# rotary_table_v2.net
KiCad netlist of a schematic drawn in Altium Designer
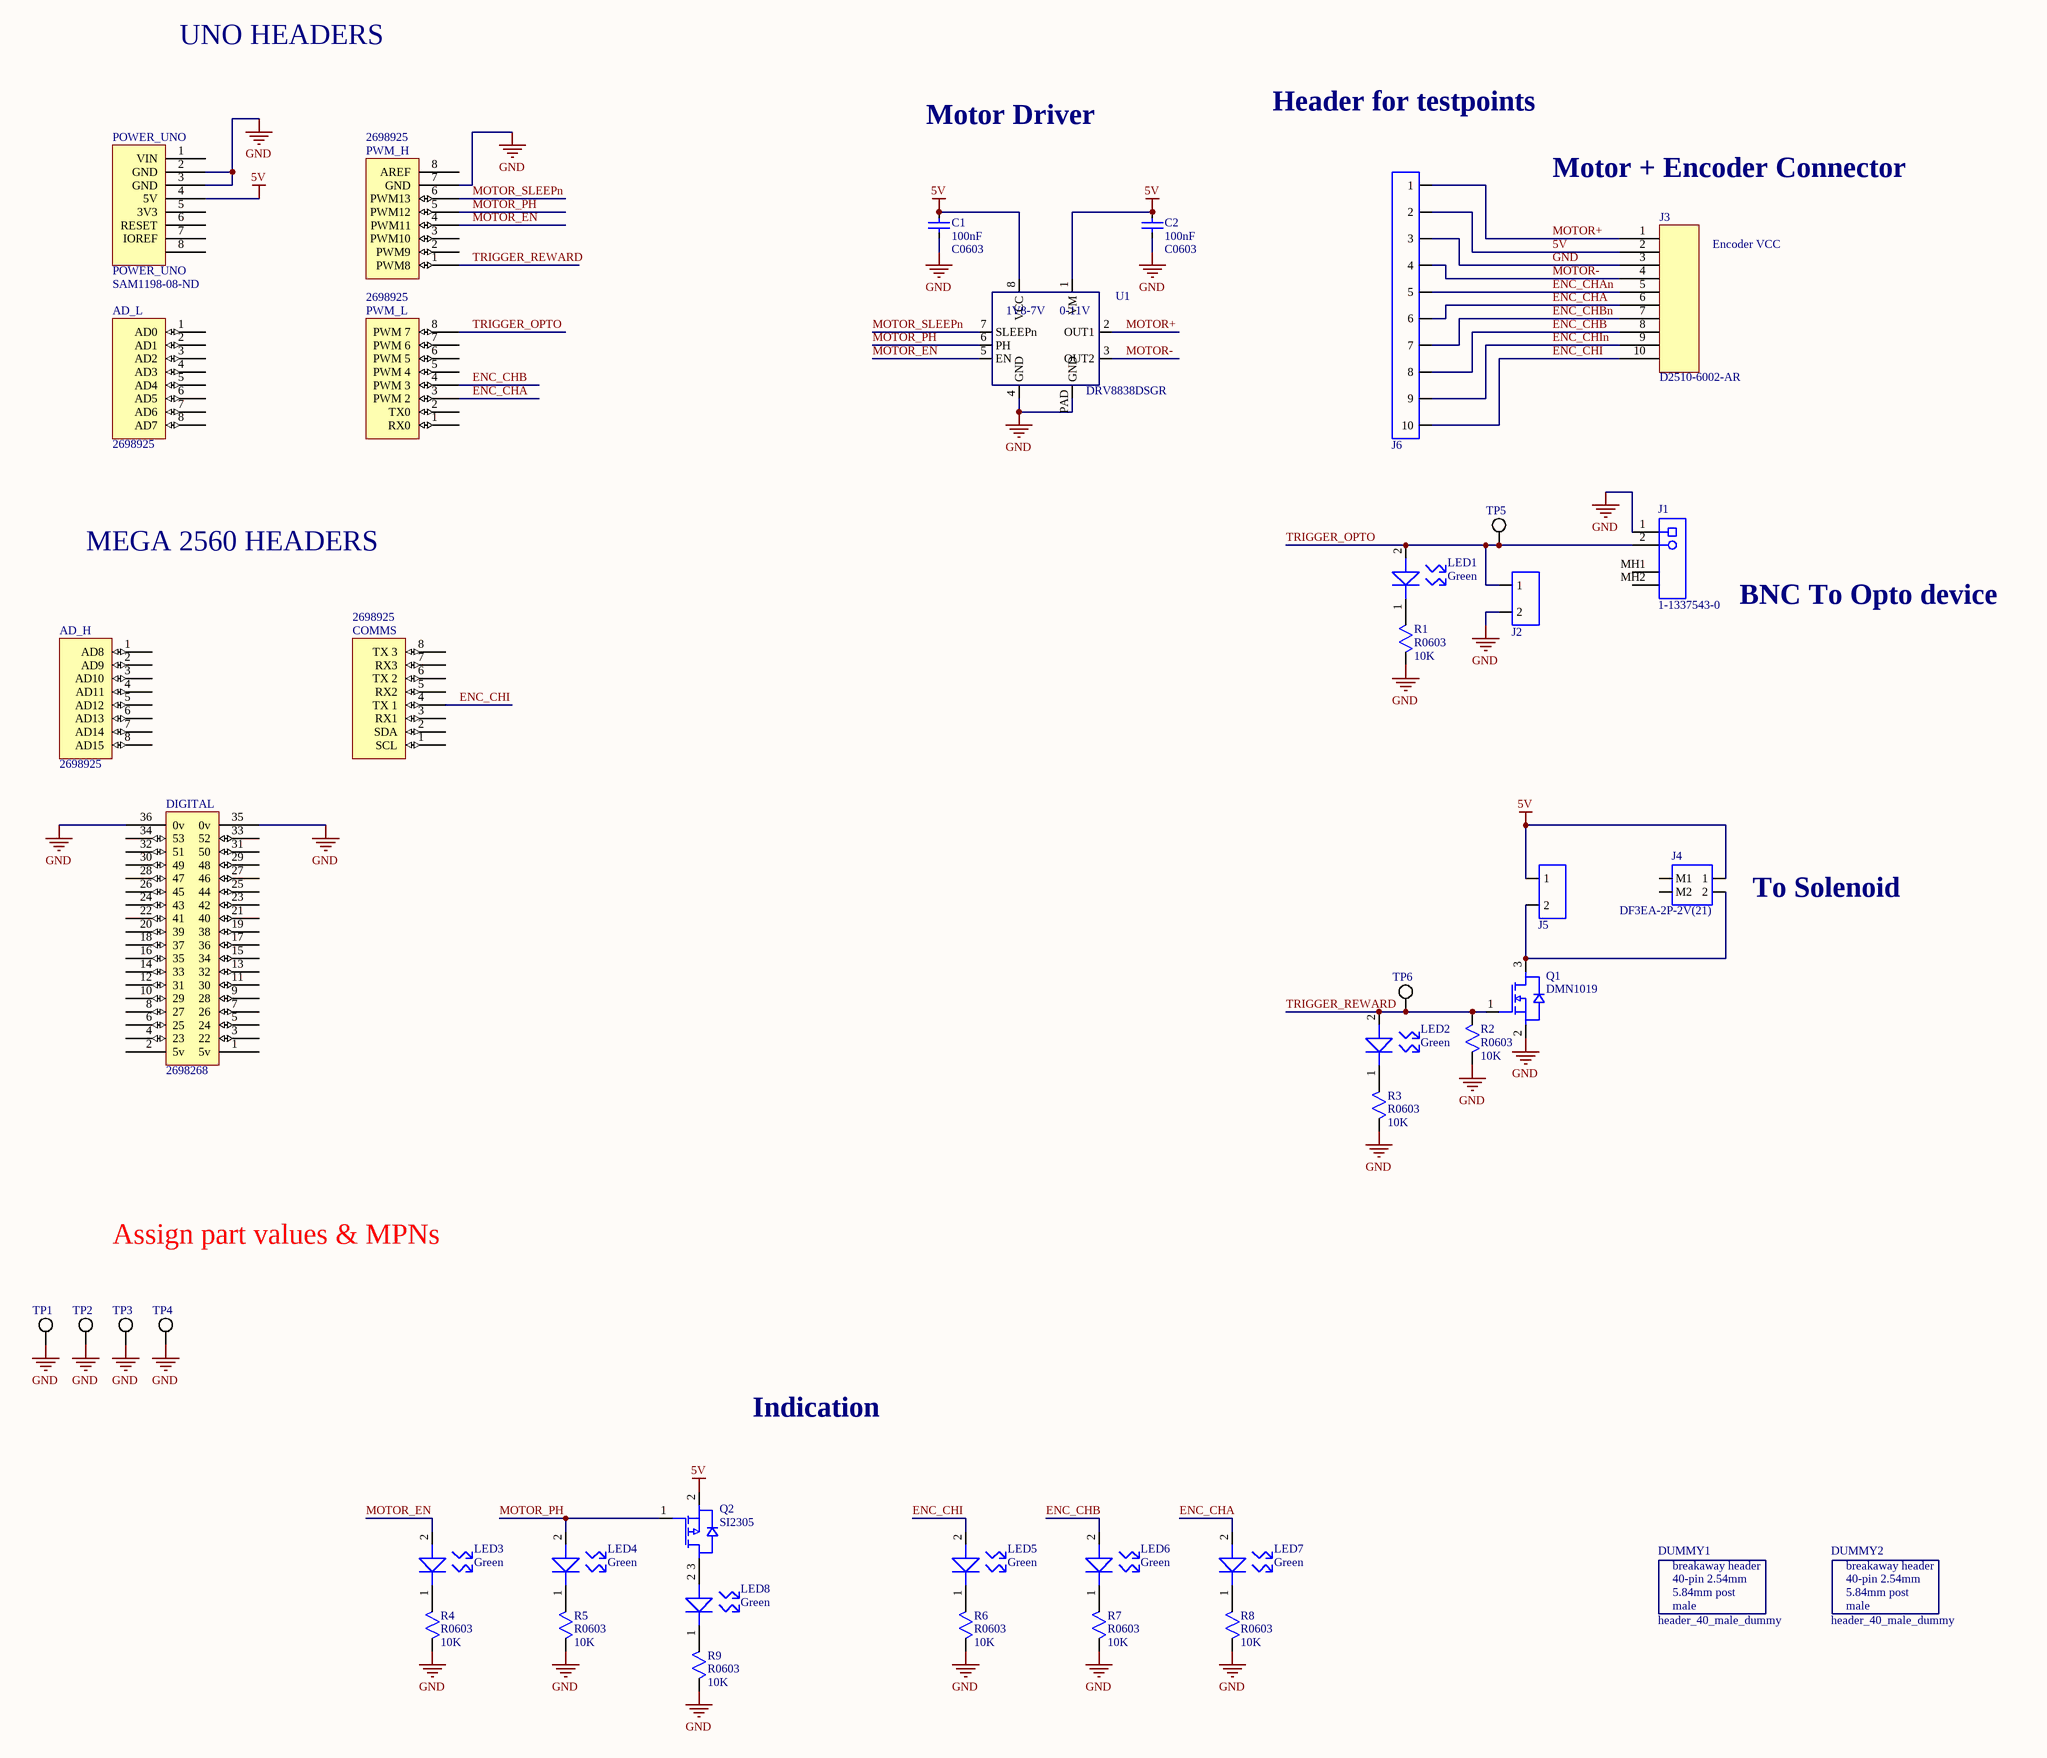
[diagram p0: rotary_table_v2.SchDoc]

(export (version "E")
  (design (tool "Eeschema 10.0.6"))
  (components
    (comp (ref "AD_H")
      (value "AD_H")
      (footprint "Header 8x1 8.5mm")
      (fields (field (name "SUPPLIER PART NUMBER 4") "2698925"))
      (libsource (lib "Header") (part "AD_H"))
    )
    (comp (ref "AD_L")
      (value "AD_L")
      (footprint "Header 8x1 8.5mm")
      (fields (field (name "SUPPLIER PART NUMBER 5") "2698925"))
      (libsource (lib "Header") (part "AD_L"))
    )
    (comp (ref "C1")
      (value "100nF")
      (footprint "C0603")
      (description "Nonpolarized capacitor")
      (fields
        (field (name "DIGIKEYPARTNUMBER") "1276-CL10B104KC8VPNCCT-ND")
        (field (name "MANUFACTURER") "Samsung")
      )
      (libsource (lib "Mark_Library") (part "CAP"))
    )
    (comp (ref "C2")
      (value "100nF")
      (footprint "C0603")
      (description "Nonpolarized capacitor")
      (fields
        (field (name "DIGIKEYPARTNUMBER") "1276-CL10B104KC8VPNCCT-ND")
        (field (name "MANUFACTURER") "Samsung")
      )
      (libsource (lib "Mark_Library") (part "CAP"))
    )
    (comp (ref "COMMS")
      (value "Communication")
      (footprint "Header 8x1 8.5mm")
      (fields (field (name "SUPPLIER PART NUMBER 4") "2698925"))
      (libsource (lib "Header") (part "Communication"))
    )
    (comp (ref "DIGITAL")
      (value "IO_36")
      (footprint "HEADER 36X 8MM")
      (fields (field (name "SUPPLIER PART NUMBER 5") "2698268"))
      (libsource (lib "Header") (part "IO_36"))
    )
    (comp (ref "DUMMY1")
      (value "header_40_male_dummy")
      (description "row of 40 pins breakaway male 2.54mm")
      (fields (field (name "MANUFACTURER") "Sullins") (field (name "MFGPARTNUMBER") "PRPC040SAAN-RC"))
      (libsource (lib "Mark_Library") (part "header_40_male_dummy"))
    )
    (comp (ref "DUMMY2")
      (value "header_40_male_dummy")
      (description "row of 40 pins breakaway male 2.54mm")
      (fields (field (name "MANUFACTURER") "Sullins") (field (name "MFGPARTNUMBER") "PRPC040SAAN-RC"))
      (libsource (lib "Mark_Library") (part "header_40_male_dummy"))
    )
    (comp (ref "J1")
      (value "1-1337543-0")
      (footprint "TECO-1-1337543-0_V")
      (fields (field (name "MANUFACTURER") "TE Connectivity") (field (name "DIGIKEYPARTNUMBER") "A97553-ND"))
      (libsource (lib "Altium Content Vault") (part "CN-1P-F-R2_A"))
    )
    (comp (ref "J2")
      (value "0.1in 2x1")
      (footprint "HEADER_2x1")
      (description "0.1in header 2x1")
      (libsource (lib "Mark_Library") (part "HEADER_2x1"))
    )
    (comp (ref "J3")
      (value "D2510-6002-AR")
      (footprint "D2510-6002")
      (description "CONN HEADER 10POS VERT 10GOLD")
      (fields
        (field (name "MANUFACTURER") "3M")
        (field (name "MANUFACTURER PART NUMBER") "D2510-6002-AR")
        (field (name "DIGIKEYPARTNUMBER") "MHC10E-ND")
      )
      (libsource (lib "UCSD Protolab") (part "D2510-6002-AR"))
    )
    (comp (ref "J4")
      (value "DF3EA-2P-2V(21)")
      (footprint "DF3EA-2P-2V(21)")
      (description "CONN HEADER SMD 2POS 2MM")
      (fields
        (field (name "MANUFACTURER") "Hirose")
        (field (name "DIGIKEYPARTNUMBER") "H125461CT-ND")
        (field (name "MFGPARTNUMBER") "DF3EA-2P-2V(21)")
      )
      (libsource (lib "Mark_Library") (part "DF3EA-2P-2V(21)"))
    )
    (comp (ref "J5")
      (value "0.1in 2x1")
      (footprint "HEADER_2x1")
      (description "0.1in header 2x1")
      (libsource (lib "Mark_Library") (part "HEADER_2x1"))
    )
    (comp (ref "J6")
      (value "0.1in 10x1")
      (footprint "HEADER_10x1")
      (description "0.1in header 10x1")
      (libsource (lib "Mark_Library") (part "HEADER_10x1"))
    )
    (comp (ref "LED1")
      (value "Green")
      (footprint "LED0603")
      (description "LED")
      (fields
        (field (name "MANUFACTURER") "Wurth Elektronik")
        (field (name "MFGPARTNUMBER") "150060VS75000")
        (field (name "COLOR") "Green")
      )
      (libsource (lib "Mark_Library") (part "LED"))
    )
    (comp (ref "LED2")
      (value "Green")
      (footprint "LED0603")
      (description "LED")
      (fields
        (field (name "MANUFACTURER") "Wurth Elektronik")
        (field (name "MFGPARTNUMBER") "150060VS75000")
        (field (name "COLOR") "Green")
      )
      (libsource (lib "Mark_Library") (part "LED"))
    )
    (comp (ref "LED3")
      (value "Green")
      (footprint "LED0603")
      (description "LED")
      (fields
        (field (name "MANUFACTURER") "Wurth Elektronik")
        (field (name "MFGPARTNUMBER") "150060VS75000")
        (field (name "COLOR") "Green")
      )
      (libsource (lib "Mark_Library") (part "LED"))
    )
    (comp (ref "LED4")
      (value "Green")
      (footprint "LED0603")
      (description "LED")
      (fields
        (field (name "MANUFACTURER") "Wurth Elektronik")
        (field (name "MFGPARTNUMBER") "150060VS75000")
        (field (name "COLOR") "Green")
      )
      (libsource (lib "Mark_Library") (part "LED"))
    )
    (comp (ref "LED5")
      (value "Green")
      (footprint "LED0603")
      (description "LED")
      (fields
        (field (name "MANUFACTURER") "Wurth Elektronik")
        (field (name "MFGPARTNUMBER") "150060VS75000")
        (field (name "COLOR") "Green")
      )
      (libsource (lib "Mark_Library") (part "LED"))
    )
    (comp (ref "LED6")
      (value "Green")
      (footprint "LED0603")
      (description "LED")
      (fields
        (field (name "MANUFACTURER") "Wurth Elektronik")
        (field (name "MFGPARTNUMBER") "150060VS75000")
        (field (name "COLOR") "Green")
      )
      (libsource (lib "Mark_Library") (part "LED"))
    )
    (comp (ref "LED7")
      (value "Green")
      (footprint "LED0603")
      (description "LED")
      (fields
        (field (name "MANUFACTURER") "Wurth Elektronik")
        (field (name "MFGPARTNUMBER") "150060VS75000")
        (field (name "COLOR") "Green")
      )
      (libsource (lib "Mark_Library") (part "LED"))
    )
    (comp (ref "LED8")
      (value "Green")
      (footprint "LED0603")
      (description "LED")
      (fields
        (field (name "MANUFACTURER") "Wurth Elektronik")
        (field (name "MFGPARTNUMBER") "150060VS75000")
        (field (name "COLOR") "Green")
      )
      (libsource (lib "Mark_Library") (part "LED"))
    )
    (comp (ref "POWER_UNO")
      (value "POWER_UNO")
      (footprint "Header 8x1 8.5mm")
      (fields (field (name "SUPPLIER PART NUMBER 2") "SAM1198-08-ND"))
      (libsource (lib "Header") (part "POWER_UNO"))
    )
    (comp (ref "PWM_H")
      (value "PWM_H")
      (footprint "Header 8x1 8.5mm")
      (fields (field (name "SUPPLIER PART NUMBER 4") "2698925"))
      (libsource (lib "Header") (part "PWM_H"))
    )
    (comp (ref "PWM_L")
      (value "PWM_L")
      (footprint "Header 8x1 8.5mm")
      (fields (field (name "SUPPLIER PART NUMBER 4") "2698925"))
      (libsource (lib "Header") (part "PWM_L"))
    )
    (comp (ref "Q1")
      (value "DMN1019")
      (footprint "SC59-3")
      (description "MOSFET N-CH 12V 9.3A SC59")
      (fields
        (field (name "MANUFACTURER") "Diodes Incorporated")
        (field (name "MFGPARTNUMBER") "DMN1019USN-7")
      )
      (libsource (lib "Mark_Library") (part "DMN1019UVT"))
    )
    (comp (ref "Q2")
      (value "SI2305")
      (footprint "SOT23-3")
      (description "P-CHANNEL MOSFET, SOT-23 PACKAGE")
      (fields (field (name "MANUFACTURER") "Micro Commercial Co") (field (name "MFGPARTNUMBER") "SI2305-TP"))
      (libsource (lib "Mark_Library") (part "SI2305"))
    )
    (comp (ref "R1")
      (value "10K")
      (footprint "R0603")
      (description "Resistor")
      (fields (field (name "MANUFACTURER") "Stackpole") (field (name "MFGPARTNUMBER") "RMCF0603FT10K0"))
      (libsource (lib "Mark_Library") (part "RES"))
    )
    (comp (ref "R2")
      (value "10K")
      (footprint "R0603")
      (description "Resistor")
      (fields (field (name "MANUFACTURER") "Stackpole") (field (name "MFGPARTNUMBER") "RMCF0603FT10K0"))
      (libsource (lib "Mark_Library") (part "RES"))
    )
    (comp (ref "R3")
      (value "10K")
      (footprint "R0603")
      (description "Resistor")
      (fields (field (name "MANUFACTURER") "Stackpole") (field (name "MFGPARTNUMBER") "RMCF0603FT10K0"))
      (libsource (lib "Mark_Library") (part "RES"))
    )
    (comp (ref "R4")
      (value "10K")
      (footprint "R0603")
      (description "Resistor")
      (fields (field (name "MANUFACTURER") "Stackpole") (field (name "MFGPARTNUMBER") "RMCF0603FT10K0"))
      (libsource (lib "Mark_Library") (part "RES"))
    )
    (comp (ref "R5")
      (value "10K")
      (footprint "R0603")
      (description "Resistor")
      (fields (field (name "MANUFACTURER") "Stackpole") (field (name "MFGPARTNUMBER") "RMCF0603FT10K0"))
      (libsource (lib "Mark_Library") (part "RES"))
    )
    (comp (ref "R6")
      (value "10K")
      (footprint "R0603")
      (description "Resistor")
      (fields (field (name "MANUFACTURER") "Stackpole") (field (name "MFGPARTNUMBER") "RMCF0603FT10K0"))
      (libsource (lib "Mark_Library") (part "RES"))
    )
    (comp (ref "R7")
      (value "10K")
      (footprint "R0603")
      (description "Resistor")
      (fields (field (name "MANUFACTURER") "Stackpole") (field (name "MFGPARTNUMBER") "RMCF0603FT10K0"))
      (libsource (lib "Mark_Library") (part "RES"))
    )
    (comp (ref "R8")
      (value "10K")
      (footprint "R0603")
      (description "Resistor")
      (fields (field (name "MANUFACTURER") "Stackpole") (field (name "MFGPARTNUMBER") "RMCF0603FT10K0"))
      (libsource (lib "Mark_Library") (part "RES"))
    )
    (comp (ref "R9")
      (value "10K")
      (footprint "R0603")
      (description "Resistor")
      (fields (field (name "MANUFACTURER") "Stackpole") (field (name "MFGPARTNUMBER") "RMCF0603FT10K0"))
      (libsource (lib "Mark_Library") (part "RES"))
    )
    (comp (ref "TP1")
      (value "GND")
      (footprint "TP_0IN1")
      (description "hole for 0.1in header. No BOM item.")
      (libsource (lib "Mark_Library") (part "TP_0IN1"))
    )
    (comp (ref "TP2")
      (value "GND")
      (footprint "TP_0IN1")
      (description "hole for 0.1in header. No BOM item.")
      (libsource (lib "Mark_Library") (part "TP_0IN1"))
    )
    (comp (ref "TP3")
      (value "GND")
      (footprint "TP_0IN1")
      (description "hole for 0.1in header. No BOM item.")
      (libsource (lib "Mark_Library") (part "TP_0IN1"))
    )
    (comp (ref "TP4")
      (value "GND")
      (footprint "TP_0IN1")
      (description "hole for 0.1in header. No BOM item.")
      (libsource (lib "Mark_Library") (part "TP_0IN1"))
    )
    (comp (ref "TP5")
      (value "OPTO")
      (footprint "TP_0IN1")
      (description "hole for 0.1in header. No BOM item.")
      (libsource (lib "Mark_Library") (part "TP_0IN1"))
    )
    (comp (ref "TP6")
      (value "REWARD")
      (footprint "TP_0IN1")
      (description "hole for 0.1in header. No BOM item.")
      (libsource (lib "Mark_Library") (part "TP_0IN1"))
    )
    (comp (ref "U1")
      (value "DRV8838DSGR")
      (footprint "WSON-8_PAD")
      (description "IC BRIDGE DRIVER PAR 8WSON")
      (fields
        (field (name "MANUFACTURER") "Texas Instruments")
        (field (name "MFGPARTNUMBER") "DRV8838DSGR")
        (field (name "DIGIKEYPARTNUMBER") "296-40081-1-ND")
      )
      (libsource (lib "Mark_Library") (part "DRV8838DSGR"))
    )
  )
  (nets
    (net (code "1") (name "/ENC_CHA") (class "Default")
      (node (ref "J3") (pin "6") (pintype "passive"))
      (node (ref "J6") (pin "6") (pinfunction "6_6") (pintype "passive"))
      (node (ref "LED7") (pin "2") (pinfunction "2_2") (pintype "passive"))
      (node (ref "PWM_L") (pin "3") (pinfunction "PWM_2_3") (pintype "bidirectional"))
    )
    (net (code "2") (name "/ENC_CHAn") (class "Default")
      (node (ref "J3") (pin "5") (pintype "passive"))
      (node (ref "J6") (pin "5") (pinfunction "5_5") (pintype "passive"))
    )
    (net (code "3") (name "/ENC_CHB") (class "Default")
      (node (ref "J3") (pin "8") (pintype "passive"))
      (node (ref "J6") (pin "8") (pinfunction "8_8") (pintype "passive"))
      (node (ref "LED6") (pin "2") (pinfunction "2_2") (pintype "passive"))
      (node (ref "PWM_L") (pin "4") (pinfunction "PWM_3_4") (pintype "bidirectional"))
    )
    (net (code "4") (name "/ENC_CHBn") (class "Default")
      (node (ref "J3") (pin "7") (pintype "passive"))
      (node (ref "J6") (pin "7") (pinfunction "7_7") (pintype "passive"))
    )
    (net (code "5") (name "/ENC_CHI") (class "Default")
      (node (ref "COMMS") (pin "4") (pinfunction "TX_1_4") (pintype "bidirectional"))
      (node (ref "J3") (pin "10") (pintype "passive"))
      (node (ref "J6") (pin "10") (pinfunction "10_10") (pintype "passive"))
      (node (ref "LED5") (pin "2") (pinfunction "2_2") (pintype "passive"))
    )
    (net (code "6") (name "/ENC_CHIn") (class "Default")
      (node (ref "J3") (pin "9") (pintype "passive"))
      (node (ref "J6") (pin "9") (pinfunction "9_9") (pintype "passive"))
    )
    (net (code "7") (name "/MOTOR+") (class "Default")
      (node (ref "J3") (pin "1") (pintype "passive"))
      (node (ref "J6") (pin "1") (pinfunction "1_1") (pintype "passive"))
      (node (ref "U1") (pin "2") (pinfunction "OUT1_2") (pintype "passive"))
    )
    (net (code "8") (name "/MOTOR-") (class "Default")
      (node (ref "J3") (pin "4") (pintype "passive"))
      (node (ref "J6") (pin "4") (pinfunction "4_4") (pintype "passive"))
      (node (ref "U1") (pin "3") (pinfunction "OUT2_3") (pintype "passive"))
    )
    (net (code "9") (name "/MOTOR_EN") (class "Default")
      (node (ref "LED3") (pin "2") (pinfunction "2_2") (pintype "passive"))
      (node (ref "PWM_H") (pin "4") (pinfunction "PWM11_4") (pintype "bidirectional"))
      (node (ref "U1") (pin "5") (pinfunction "EN_5") (pintype "passive"))
    )
    (net (code "10") (name "/MOTOR_PH") (class "Default")
      (node (ref "LED4") (pin "2") (pinfunction "2_2") (pintype "passive"))
      (node (ref "PWM_H") (pin "5") (pinfunction "PWM12_5") (pintype "bidirectional"))
      (node (ref "Q2") (pin "1") (pinfunction "1_1") (pintype "passive"))
      (node (ref "U1") (pin "6") (pinfunction "PH_6") (pintype "passive"))
    )
    (net (code "11") (name "/MOTOR_SLEEPn") (class "Default")
      (node (ref "PWM_H") (pin "6") (pinfunction "PWM13_6") (pintype "bidirectional"))
      (node (ref "U1") (pin "7") (pinfunction "SLEEPn_7") (pintype "passive"))
    )
    (net (code "12") (name "/TRIGGER_OPTO") (class "Default")
      (node (ref "J1") (pin "2") (pinfunction "2_2") (pintype "passive"))
      (node (ref "J2") (pin "1") (pinfunction "1_1") (pintype "passive"))
      (node (ref "LED1") (pin "2") (pinfunction "2_2") (pintype "passive"))
      (node (ref "PWM_L") (pin "8") (pinfunction "PWM_7_8") (pintype "bidirectional"))
      (node (ref "TP5") (pin "1") (pinfunction "MTG_1") (pintype "passive"))
    )
    (net (code "13") (name "/TRIGGER_REWARD") (class "Default")
      (node (ref "LED2") (pin "2") (pinfunction "2_2") (pintype "passive"))
      (node (ref "PWM_H") (pin "1") (pinfunction "PWM8_1") (pintype "bidirectional"))
      (node (ref "Q1") (pin "1") (pinfunction "1_1") (pintype "passive"))
      (node (ref "R2") (pin "1") (pinfunction "1_1") (pintype "passive"))
      (node (ref "TP6") (pin "1") (pinfunction "MTG_1") (pintype "passive"))
    )
    (net (code "14") (name "5V") (class "Default")
      (node (ref "C1") (pin "2") (pinfunction "2_2") (pintype "passive"))
      (node (ref "C2") (pin "2") (pinfunction "2_2") (pintype "passive"))
      (node (ref "J3") (pin "2") (pintype "passive"))
      (node (ref "J4") (pin "1") (pinfunction "1_1") (pintype "passive"))
      (node (ref "J5") (pin "1") (pinfunction "1_1") (pintype "passive"))
      (node (ref "J6") (pin "2") (pinfunction "2_2") (pintype "passive"))
      (node (ref "POWER_UNO") (pin "4") (pinfunction "5V_4") (pintype "power_in"))
      (node (ref "Q2") (pin "2") (pinfunction "2_2") (pintype "passive"))
      (node (ref "U1") (pin "1") (pinfunction "VM_1") (pintype "passive"))
      (node (ref "U1") (pin "8") (pinfunction "VCC_8") (pintype "passive"))
    )
    (net (code "15") (name "GND") (class "Default")
      (node (ref "C1") (pin "1") (pinfunction "1_1") (pintype "passive"))
      (node (ref "C2") (pin "1") (pinfunction "1_1") (pintype "passive"))
      (node (ref "DIGITAL") (pin "35") (pinfunction "0v_35") (pintype "power_in"))
      (node (ref "DIGITAL") (pin "36") (pinfunction "0v_36") (pintype "power_in"))
      (node (ref "J1") (pin "1") (pinfunction "1_1") (pintype "passive"))
      (node (ref "J2") (pin "2") (pinfunction "2_2") (pintype "passive"))
      (node (ref "J3") (pin "3") (pintype "passive"))
      (node (ref "J6") (pin "3") (pinfunction "3_3") (pintype "passive"))
      (node (ref "POWER_UNO") (pin "2") (pinfunction "GND_2") (pintype "power_in"))
      (node (ref "POWER_UNO") (pin "3") (pinfunction "GND_3") (pintype "power_in"))
      (node (ref "PWM_H") (pin "7") (pinfunction "GND_7") (pintype "power_in"))
      (node (ref "Q1") (pin "2") (pinfunction "2_2") (pintype "passive"))
      (node (ref "R1") (pin "2") (pinfunction "2_2") (pintype "passive"))
      (node (ref "R2") (pin "2") (pinfunction "2_2") (pintype "passive"))
      (node (ref "R3") (pin "2") (pinfunction "2_2") (pintype "passive"))
      (node (ref "R4") (pin "2") (pinfunction "2_2") (pintype "passive"))
      (node (ref "R5") (pin "2") (pinfunction "2_2") (pintype "passive"))
      (node (ref "R6") (pin "2") (pinfunction "2_2") (pintype "passive"))
      (node (ref "R7") (pin "2") (pinfunction "2_2") (pintype "passive"))
      (node (ref "R8") (pin "2") (pinfunction "2_2") (pintype "passive"))
      (node (ref "R9") (pin "2") (pinfunction "2_2") (pintype "passive"))
      (node (ref "TP1") (pin "1") (pinfunction "MTG_1") (pintype "passive"))
      (node (ref "TP2") (pin "1") (pinfunction "MTG_1") (pintype "passive"))
      (node (ref "TP3") (pin "1") (pinfunction "MTG_1") (pintype "passive"))
      (node (ref "TP4") (pin "1") (pinfunction "MTG_1") (pintype "passive"))
      (node (ref "U1") (pin "4") (pinfunction "GND_4") (pintype "passive"))
      (node (ref "U1") (pin "PAD") (pinfunction "GND_PAD") (pintype "passive"))
    )
    (net (code "16") (name "Net-(J4-Pad2)") (class "Default")
      (node (ref "J4") (pin "2") (pinfunction "2_2") (pintype "passive"))
      (node (ref "J5") (pin "2") (pinfunction "2_2") (pintype "passive"))
      (node (ref "Q1") (pin "3") (pinfunction "3_3") (pintype "passive"))
    )
    (net (code "17") (name "Net-(LED1-Pad1)") (class "Default")
      (node (ref "LED1") (pin "1") (pinfunction "1_1") (pintype "passive"))
      (node (ref "R1") (pin "1") (pinfunction "1_1") (pintype "passive"))
    )
    (net (code "18") (name "Net-(LED2-Pad1)") (class "Default")
      (node (ref "LED2") (pin "1") (pinfunction "1_1") (pintype "passive"))
      (node (ref "R3") (pin "1") (pinfunction "1_1") (pintype "passive"))
    )
    (net (code "19") (name "Net-(LED3-Pad1)") (class "Default")
      (node (ref "LED3") (pin "1") (pinfunction "1_1") (pintype "passive"))
      (node (ref "R4") (pin "1") (pinfunction "1_1") (pintype "passive"))
    )
    (net (code "20") (name "Net-(LED4-Pad1)") (class "Default")
      (node (ref "LED4") (pin "1") (pinfunction "1_1") (pintype "passive"))
      (node (ref "R5") (pin "1") (pinfunction "1_1") (pintype "passive"))
    )
    (net (code "21") (name "Net-(LED5-Pad1)") (class "Default")
      (node (ref "LED5") (pin "1") (pinfunction "1_1") (pintype "passive"))
      (node (ref "R6") (pin "1") (pinfunction "1_1") (pintype "passive"))
    )
    (net (code "22") (name "Net-(LED6-Pad1)") (class "Default")
      (node (ref "LED6") (pin "1") (pinfunction "1_1") (pintype "passive"))
      (node (ref "R7") (pin "1") (pinfunction "1_1") (pintype "passive"))
    )
    (net (code "23") (name "Net-(LED7-Pad1)") (class "Default")
      (node (ref "LED7") (pin "1") (pinfunction "1_1") (pintype "passive"))
      (node (ref "R8") (pin "1") (pinfunction "1_1") (pintype "passive"))
    )
    (net (code "24") (name "Net-(LED8-Pad1)") (class "Default")
      (node (ref "LED8") (pin "1") (pinfunction "1_1") (pintype "passive"))
      (node (ref "R9") (pin "1") (pinfunction "1_1") (pintype "passive"))
    )
    (net (code "25") (name "Net-(LED8-Pad2)") (class "Default")
      (node (ref "LED8") (pin "2") (pinfunction "2_2") (pintype "passive"))
      (node (ref "Q2") (pin "3") (pinfunction "3_3") (pintype "passive"))
    )
    (net (code "26") (name "unconnected-(AD_H-AD8-Pad1)") (class "Default")
      (node (ref "AD_H") (pin "1") (pinfunction "AD8_1") (pintype "bidirectional"))
    )
    (net (code "27") (name "unconnected-(AD_H-AD9-Pad2)") (class "Default")
      (node (ref "AD_H") (pin "2") (pinfunction "AD9_2") (pintype "bidirectional"))
    )
    (net (code "28") (name "unconnected-(AD_H-AD10-Pad3)") (class "Default")
      (node (ref "AD_H") (pin "3") (pinfunction "AD10_3") (pintype "bidirectional"))
    )
    (net (code "29") (name "unconnected-(AD_H-AD11-Pad4)") (class "Default")
      (node (ref "AD_H") (pin "4") (pinfunction "AD11_4") (pintype "bidirectional"))
    )
    (net (code "30") (name "unconnected-(AD_H-AD12-Pad5)") (class "Default")
      (node (ref "AD_H") (pin "5") (pinfunction "AD12_5") (pintype "bidirectional"))
    )
    (net (code "31") (name "unconnected-(AD_H-AD13-Pad6)") (class "Default")
      (node (ref "AD_H") (pin "6") (pinfunction "AD13_6") (pintype "bidirectional"))
    )
    (net (code "32") (name "unconnected-(AD_H-AD14-Pad7)") (class "Default")
      (node (ref "AD_H") (pin "7") (pinfunction "AD14_7") (pintype "bidirectional"))
    )
    (net (code "33") (name "unconnected-(AD_H-AD15-Pad8)") (class "Default")
      (node (ref "AD_H") (pin "8") (pinfunction "AD15_8") (pintype "bidirectional"))
    )
    (net (code "34") (name "unconnected-(AD_L-AD0-Pad1)") (class "Default")
      (node (ref "AD_L") (pin "1") (pinfunction "AD0_1") (pintype "bidirectional"))
    )
    (net (code "35") (name "unconnected-(AD_L-AD1-Pad2)") (class "Default")
      (node (ref "AD_L") (pin "2") (pinfunction "AD1_2") (pintype "bidirectional"))
    )
    (net (code "36") (name "unconnected-(AD_L-AD2-Pad3)") (class "Default")
      (node (ref "AD_L") (pin "3") (pinfunction "AD2_3") (pintype "bidirectional"))
    )
    (net (code "37") (name "unconnected-(AD_L-AD3-Pad4)") (class "Default")
      (node (ref "AD_L") (pin "4") (pinfunction "AD3_4") (pintype "bidirectional"))
    )
    (net (code "38") (name "unconnected-(AD_L-AD4-Pad5)") (class "Default")
      (node (ref "AD_L") (pin "5") (pinfunction "AD4_5") (pintype "bidirectional"))
    )
    (net (code "39") (name "unconnected-(AD_L-AD5-Pad6)") (class "Default")
      (node (ref "AD_L") (pin "6") (pinfunction "AD5_6") (pintype "bidirectional"))
    )
    (net (code "40") (name "unconnected-(AD_L-AD6-Pad7)") (class "Default")
      (node (ref "AD_L") (pin "7") (pinfunction "AD6_7") (pintype "bidirectional"))
    )
    (net (code "41") (name "unconnected-(AD_L-AD7-Pad8)") (class "Default")
      (node (ref "AD_L") (pin "8") (pinfunction "AD7_8") (pintype "bidirectional"))
    )
    (net (code "42") (name "unconnected-(COMMS-RX1-Pad3)") (class "Default")
      (node (ref "COMMS") (pin "3") (pinfunction "RX1_3") (pintype "bidirectional"))
    )
    (net (code "43") (name "unconnected-(COMMS-RX2-Pad5)") (class "Default")
      (node (ref "COMMS") (pin "5") (pinfunction "RX2_5") (pintype "bidirectional"))
    )
    (net (code "44") (name "unconnected-(COMMS-RX3-Pad7)") (class "Default")
      (node (ref "COMMS") (pin "7") (pinfunction "RX3_7") (pintype "bidirectional"))
    )
    (net (code "45") (name "unconnected-(COMMS-SCL-Pad1)") (class "Default")
      (node (ref "COMMS") (pin "1") (pinfunction "SCL_1") (pintype "bidirectional"))
    )
    (net (code "46") (name "unconnected-(COMMS-SDA-Pad2)") (class "Default")
      (node (ref "COMMS") (pin "2") (pinfunction "SDA_2") (pintype "bidirectional"))
    )
    (net (code "47") (name "unconnected-(COMMS-TX_2-Pad6)") (class "Default")
      (node (ref "COMMS") (pin "6") (pinfunction "TX_2_6") (pintype "bidirectional"))
    )
    (net (code "48") (name "unconnected-(COMMS-TX_3-Pad8)") (class "Default")
      (node (ref "COMMS") (pin "8") (pinfunction "TX_3_8") (pintype "bidirectional"))
    )
    (net (code "49") (name "unconnected-(DIGITAL-5v-Pad1)") (class "Default")
      (node (ref "DIGITAL") (pin "1") (pinfunction "5v_1") (pintype "power_in"))
    )
    (net (code "50") (name "unconnected-(DIGITAL-5v-Pad2)") (class "Default")
      (node (ref "DIGITAL") (pin "2") (pinfunction "5v_2") (pintype "power_in"))
    )
    (net (code "51") (name "unconnected-(DIGITAL-22-Pad3)") (class "Default")
      (node (ref "DIGITAL") (pin "3") (pinfunction "22_3") (pintype "bidirectional"))
    )
    (net (code "52") (name "unconnected-(DIGITAL-23-Pad4)") (class "Default")
      (node (ref "DIGITAL") (pin "4") (pinfunction "23_4") (pintype "bidirectional"))
    )
    (net (code "53") (name "unconnected-(DIGITAL-24-Pad5)") (class "Default")
      (node (ref "DIGITAL") (pin "5") (pinfunction "24_5") (pintype "bidirectional"))
    )
    (net (code "54") (name "unconnected-(DIGITAL-25-Pad6)") (class "Default")
      (node (ref "DIGITAL") (pin "6") (pinfunction "25_6") (pintype "bidirectional"))
    )
    (net (code "55") (name "unconnected-(DIGITAL-26-Pad7)") (class "Default")
      (node (ref "DIGITAL") (pin "7") (pinfunction "26_7") (pintype "bidirectional"))
    )
    (net (code "56") (name "unconnected-(DIGITAL-27-Pad8)") (class "Default")
      (node (ref "DIGITAL") (pin "8") (pinfunction "27_8") (pintype "bidirectional"))
    )
    (net (code "57") (name "unconnected-(DIGITAL-28-Pad9)") (class "Default")
      (node (ref "DIGITAL") (pin "9") (pinfunction "28_9") (pintype "bidirectional"))
    )
    (net (code "58") (name "unconnected-(DIGITAL-29-Pad10)") (class "Default")
      (node (ref "DIGITAL") (pin "10") (pinfunction "29_10") (pintype "bidirectional"))
    )
    (net (code "59") (name "unconnected-(DIGITAL-30-Pad11)") (class "Default")
      (node (ref "DIGITAL") (pin "11") (pinfunction "30_11") (pintype "bidirectional"))
    )
    (net (code "60") (name "unconnected-(DIGITAL-31-Pad12)") (class "Default")
      (node (ref "DIGITAL") (pin "12") (pinfunction "31_12") (pintype "bidirectional"))
    )
    (net (code "61") (name "unconnected-(DIGITAL-32-Pad13)") (class "Default")
      (node (ref "DIGITAL") (pin "13") (pinfunction "32_13") (pintype "bidirectional"))
    )
    (net (code "62") (name "unconnected-(DIGITAL-33-Pad14)") (class "Default")
      (node (ref "DIGITAL") (pin "14") (pinfunction "33_14") (pintype "bidirectional"))
    )
    (net (code "63") (name "unconnected-(DIGITAL-34-Pad15)") (class "Default")
      (node (ref "DIGITAL") (pin "15") (pinfunction "34_15") (pintype "bidirectional"))
    )
    (net (code "64") (name "unconnected-(DIGITAL-35-Pad16)") (class "Default")
      (node (ref "DIGITAL") (pin "16") (pinfunction "35_16") (pintype "bidirectional"))
    )
    (net (code "65") (name "unconnected-(DIGITAL-36-Pad17)") (class "Default")
      (node (ref "DIGITAL") (pin "17") (pinfunction "36_17") (pintype "bidirectional"))
    )
    (net (code "66") (name "unconnected-(DIGITAL-37-Pad18)") (class "Default")
      (node (ref "DIGITAL") (pin "18") (pinfunction "37_18") (pintype "bidirectional"))
    )
    (net (code "67") (name "unconnected-(DIGITAL-38-Pad19)") (class "Default")
      (node (ref "DIGITAL") (pin "19") (pinfunction "38_19") (pintype "bidirectional"))
    )
    (net (code "68") (name "unconnected-(DIGITAL-39-Pad20)") (class "Default")
      (node (ref "DIGITAL") (pin "20") (pinfunction "39_20") (pintype "bidirectional"))
    )
    (net (code "69") (name "unconnected-(DIGITAL-40-Pad21)") (class "Default")
      (node (ref "DIGITAL") (pin "21") (pinfunction "40_21") (pintype "bidirectional"))
    )
    (net (code "70") (name "unconnected-(DIGITAL-41-Pad22)") (class "Default")
      (node (ref "DIGITAL") (pin "22") (pinfunction "41_22") (pintype "bidirectional"))
    )
    (net (code "71") (name "unconnected-(DIGITAL-42-Pad23)") (class "Default")
      (node (ref "DIGITAL") (pin "23") (pinfunction "42_23") (pintype "bidirectional"))
    )
    (net (code "72") (name "unconnected-(DIGITAL-43-Pad24)") (class "Default")
      (node (ref "DIGITAL") (pin "24") (pinfunction "43_24") (pintype "bidirectional"))
    )
    (net (code "73") (name "unconnected-(DIGITAL-44-Pad25)") (class "Default")
      (node (ref "DIGITAL") (pin "25") (pinfunction "44_25") (pintype "bidirectional"))
    )
    (net (code "74") (name "unconnected-(DIGITAL-45-Pad26)") (class "Default")
      (node (ref "DIGITAL") (pin "26") (pinfunction "45_26") (pintype "bidirectional"))
    )
    (net (code "75") (name "unconnected-(DIGITAL-46-Pad27)") (class "Default")
      (node (ref "DIGITAL") (pin "27") (pinfunction "46_27") (pintype "bidirectional"))
    )
    (net (code "76") (name "unconnected-(DIGITAL-47-Pad28)") (class "Default")
      (node (ref "DIGITAL") (pin "28") (pinfunction "47_28") (pintype "bidirectional"))
    )
    (net (code "77") (name "unconnected-(DIGITAL-48-Pad29)") (class "Default")
      (node (ref "DIGITAL") (pin "29") (pinfunction "48_29") (pintype "bidirectional"))
    )
    (net (code "78") (name "unconnected-(DIGITAL-49-Pad30)") (class "Default")
      (node (ref "DIGITAL") (pin "30") (pinfunction "49_30") (pintype "bidirectional"))
    )
    (net (code "79") (name "unconnected-(DIGITAL-50-Pad31)") (class "Default")
      (node (ref "DIGITAL") (pin "31") (pinfunction "50_31") (pintype "bidirectional"))
    )
    (net (code "80") (name "unconnected-(DIGITAL-51-Pad32)") (class "Default")
      (node (ref "DIGITAL") (pin "32") (pinfunction "51_32") (pintype "bidirectional"))
    )
    (net (code "81") (name "unconnected-(DIGITAL-52-Pad33)") (class "Default")
      (node (ref "DIGITAL") (pin "33") (pinfunction "52_33") (pintype "bidirectional"))
    )
    (net (code "82") (name "unconnected-(DIGITAL-53-Pad34)") (class "Default")
      (node (ref "DIGITAL") (pin "34") (pinfunction "53_34") (pintype "bidirectional"))
    )
    (net (code "83") (name "unconnected-(J1-PadMH1)") (class "Default")
      (node (ref "J1") (pin "MH1") (pinfunction "MH1_MH1") (pintype "passive"))
    )
    (net (code "84") (name "unconnected-(J1-PadMH2)") (class "Default")
      (node (ref "J1") (pin "MH2") (pinfunction "MH2_MH2") (pintype "passive"))
    )
    (net (code "85") (name "unconnected-(J4-PadM1)") (class "Default")
      (node (ref "J4") (pin "M1") (pinfunction "M1_M1") (pintype "passive"))
    )
    (net (code "86") (name "unconnected-(J4-PadM2)") (class "Default")
      (node (ref "J4") (pin "M2") (pinfunction "M2_M2") (pintype "passive"))
    )
    (net (code "87") (name "unconnected-(POWER_UNO-3V3-Pad5)") (class "Default")
      (node (ref "POWER_UNO") (pin "5") (pinfunction "3V3_5") (pintype "power_in"))
    )
    (net (code "88") (name "unconnected-(POWER_UNO-IOREF-Pad7)") (class "Default")
      (node (ref "POWER_UNO") (pin "7") (pinfunction "IOREF_7") (pintype "power_in"))
    )
    (net (code "89") (name "unconnected-(POWER_UNO-Pad8)") (class "Default")
      (node (ref "POWER_UNO") (pin "8") (pintype "passive"))
    )
    (net (code "90") (name "unconnected-(POWER_UNO-RESET-Pad6)") (class "Default")
      (node (ref "POWER_UNO") (pin "6") (pinfunction "RESET_6") (pintype "passive"))
    )
    (net (code "91") (name "unconnected-(POWER_UNO-VIN-Pad1)") (class "Default")
      (node (ref "POWER_UNO") (pin "1") (pinfunction "VIN_1") (pintype "power_in"))
    )
    (net (code "92") (name "unconnected-(PWM_H-AREF-Pad8)") (class "Default")
      (node (ref "PWM_H") (pin "8") (pinfunction "AREF_8") (pintype "passive"))
    )
    (net (code "93") (name "unconnected-(PWM_H-PWM9-Pad2)") (class "Default")
      (node (ref "PWM_H") (pin "2") (pinfunction "PWM9_2") (pintype "bidirectional"))
    )
    (net (code "94") (name "unconnected-(PWM_H-PWM10-Pad3)") (class "Default")
      (node (ref "PWM_H") (pin "3") (pinfunction "PWM10_3") (pintype "bidirectional"))
    )
    (net (code "95") (name "unconnected-(PWM_L-PWM_4-Pad5)") (class "Default")
      (node (ref "PWM_L") (pin "5") (pinfunction "PWM_4_5") (pintype "bidirectional"))
    )
    (net (code "96") (name "unconnected-(PWM_L-PWM_5-Pad6)") (class "Default")
      (node (ref "PWM_L") (pin "6") (pinfunction "PWM_5_6") (pintype "bidirectional"))
    )
    (net (code "97") (name "unconnected-(PWM_L-PWM_6-Pad7)") (class "Default")
      (node (ref "PWM_L") (pin "7") (pinfunction "PWM_6_7") (pintype "bidirectional"))
    )
    (net (code "98") (name "unconnected-(PWM_L-RX0-Pad1)") (class "Default")
      (node (ref "PWM_L") (pin "1") (pinfunction "RX0_1") (pintype "bidirectional"))
    )
    (net (code "99") (name "unconnected-(PWM_L-TX0-Pad2)") (class "Default")
      (node (ref "PWM_L") (pin "2") (pinfunction "TX0_2") (pintype "bidirectional"))
    )
  )
)
